# schematic.net
KiCad netlist of a schematic drawn in EasyEDA
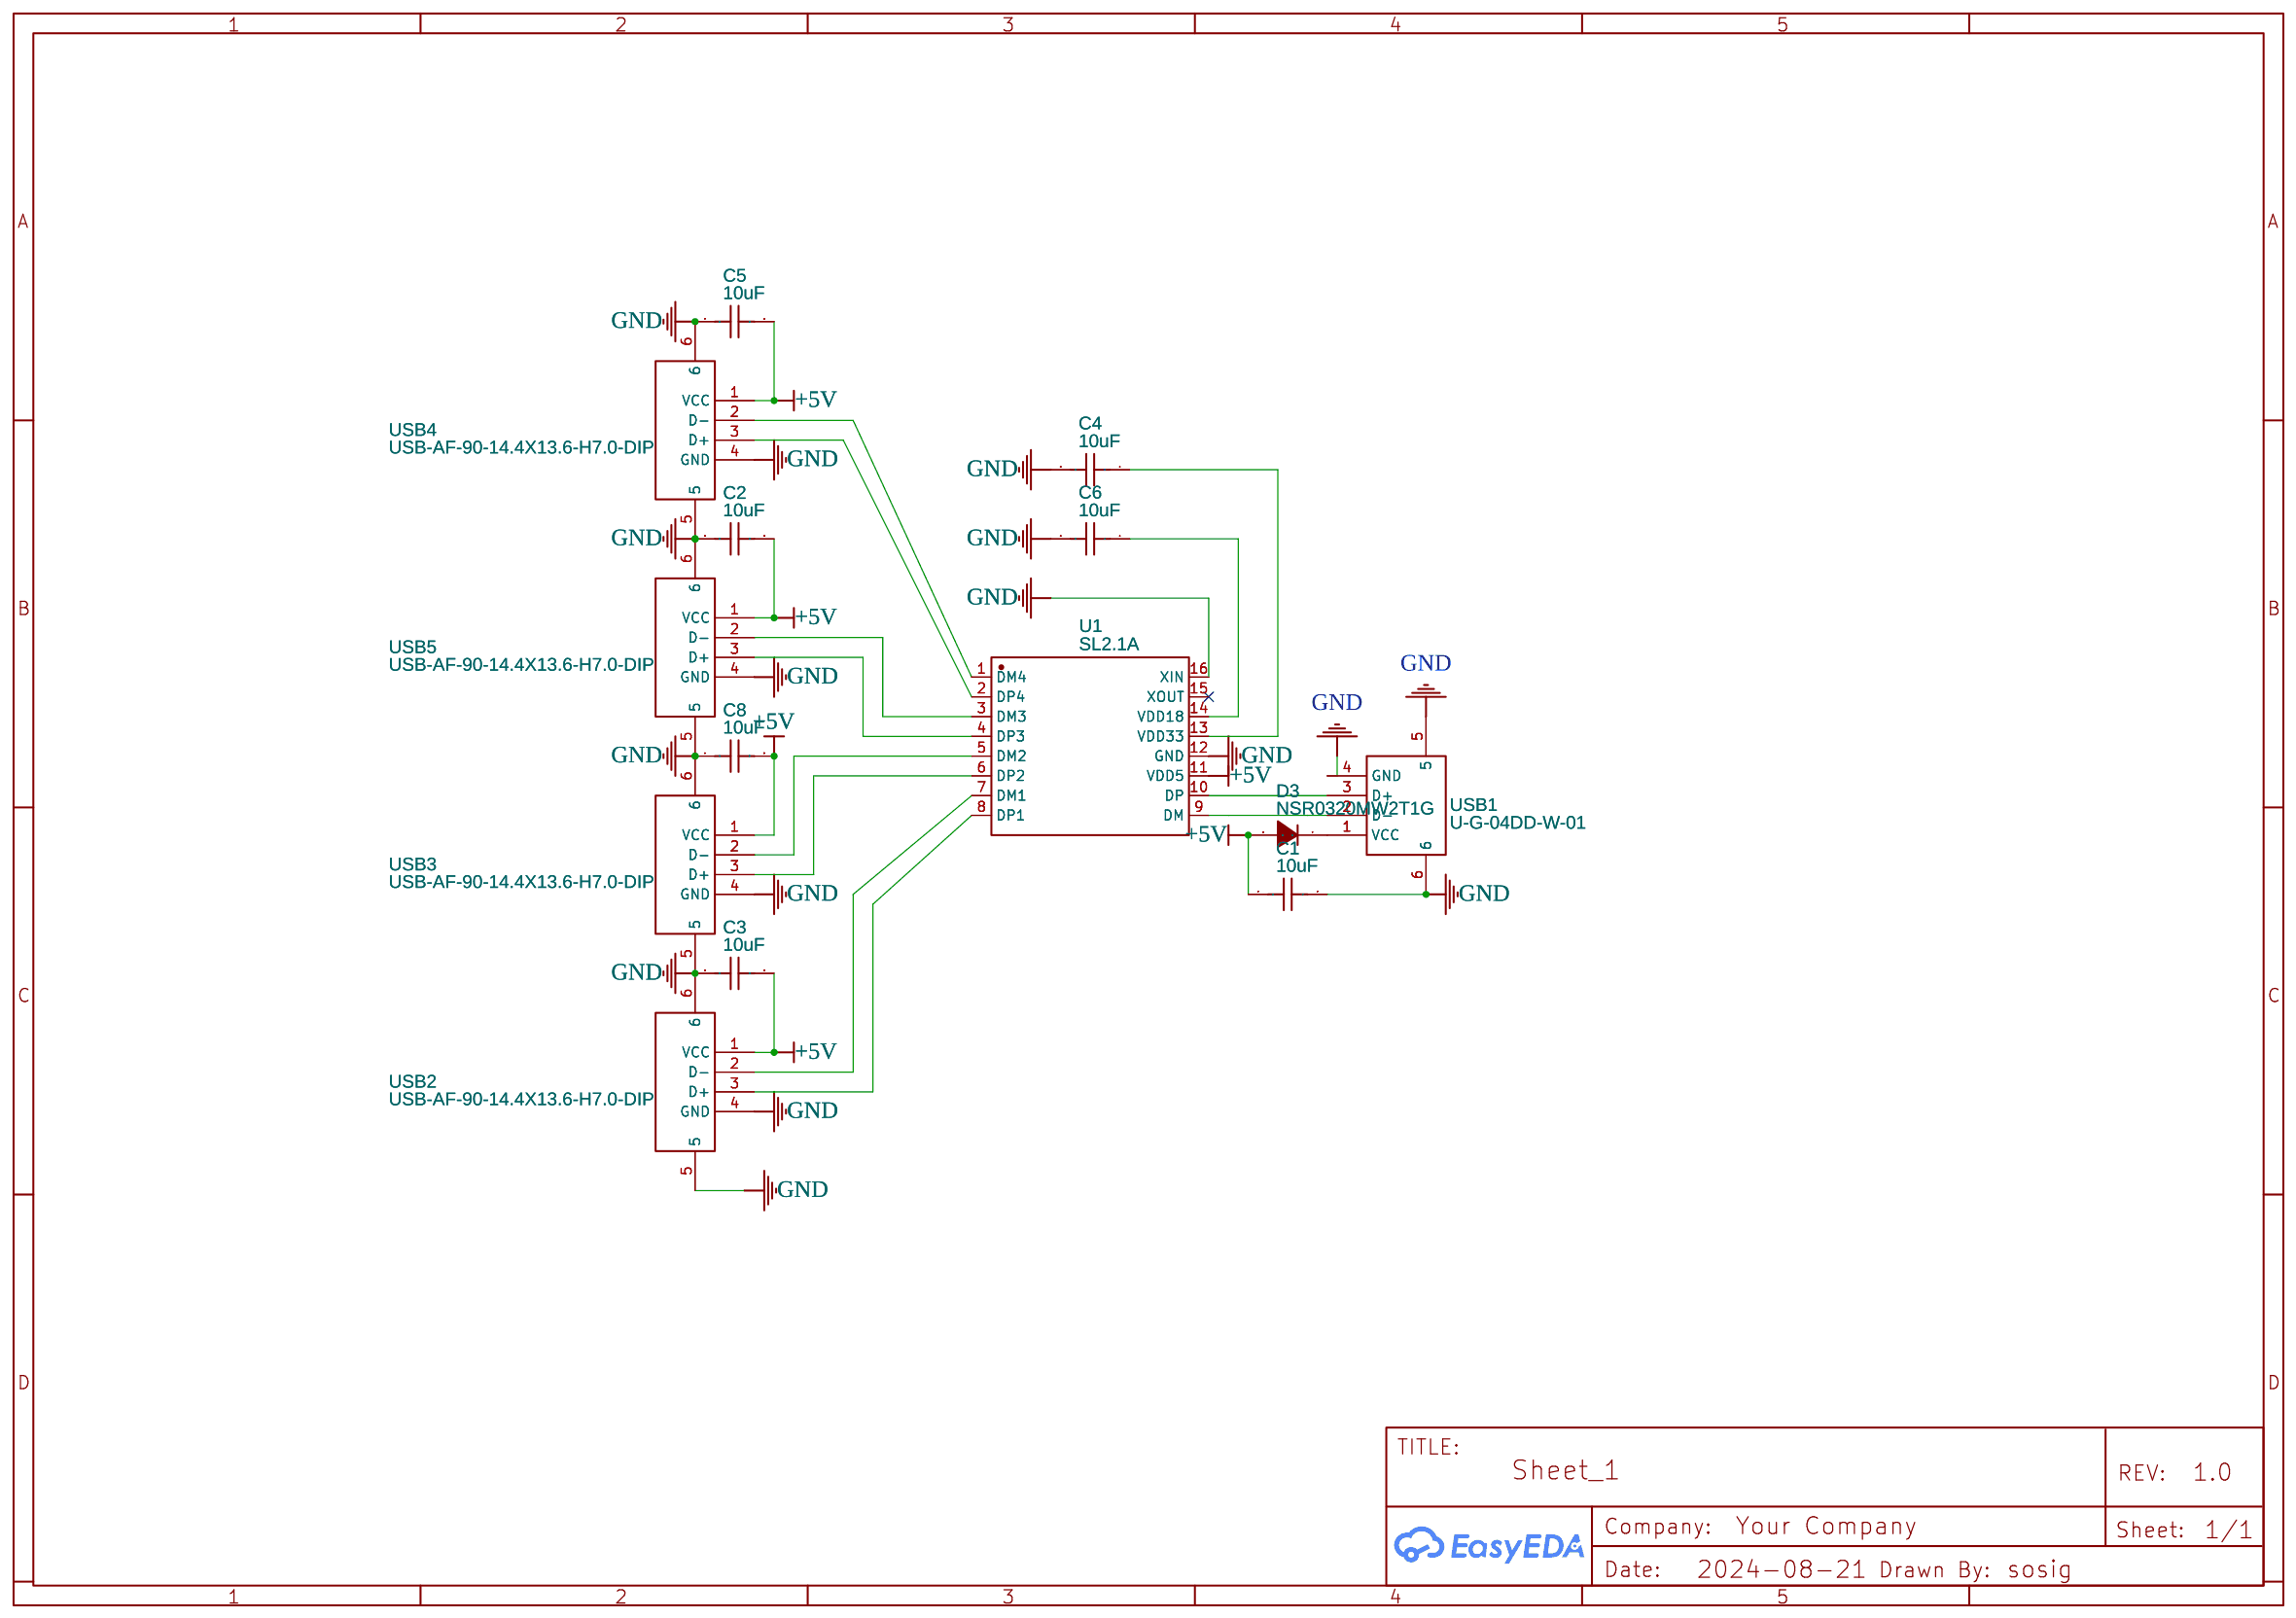
[diagram p0: schematic sheet]

(export (version "E")
  (design (tool "Eeschema 10.0.6"))
  (components
    (comp (ref "C1")
      (value "10uF")
      (fields
        (field (name "Manufacturer Part") "CL10A106KP8NNNC")
        (field (name "Manufacturer") "SAMSUNG(三星)")
      )
      (libsource (lib "") (part "CL10A106KP8NNNC"))
    )
    (comp (ref "C2")
      (value "10uF")
      (fields
        (field (name "Manufacturer Part") "CL10A106KP8NNNC")
        (field (name "Manufacturer") "SAMSUNG(三星)")
      )
      (libsource (lib "") (part "CL10A106KP8NNNC"))
    )
    (comp (ref "C3")
      (value "10uF")
      (fields
        (field (name "Manufacturer Part") "CL10A106KP8NNNC")
        (field (name "Manufacturer") "SAMSUNG(三星)")
      )
      (libsource (lib "") (part "CL10A106KP8NNNC"))
    )
    (comp (ref "C4")
      (value "10uF")
      (fields
        (field (name "Manufacturer Part") "CL10A106KP8NNNC")
        (field (name "Manufacturer") "SAMSUNG(三星)")
      )
      (libsource (lib "") (part "CL10A106KP8NNNC_1"))
    )
    (comp (ref "C5")
      (value "10uF")
      (fields
        (field (name "Manufacturer Part") "CL10A106KP8NNNC")
        (field (name "Manufacturer") "SAMSUNG(三星)")
      )
      (libsource (lib "") (part "CL10A106KP8NNNC"))
    )
    (comp (ref "C6")
      (value "10uF")
      (fields
        (field (name "Manufacturer Part") "CL10A106KP8NNNC")
        (field (name "Manufacturer") "SAMSUNG(三星)")
      )
      (libsource (lib "") (part "CL10A106KP8NNNC_1"))
    )
    (comp (ref "C8")
      (value "10uF")
      (fields
        (field (name "Manufacturer Part") "CL10A106KP8NNNC")
        (field (name "Manufacturer") "SAMSUNG(三星)")
      )
      (libsource (lib "") (part "CL10A106KP8NNNC"))
    )
    (comp (ref "D3")
      (value "NSR0320MW2T1G")
      (fields (field (name "Manufacturer") "onsemi(安森美)"))
      (libsource (lib "") (part "NSR0320MW2T1G"))
    )
    (comp (ref "U1")
      (value "SL2.1A")
      (fields (field (name "Manufacturer") "CoreChips(和芯润德)"))
      (libsource (lib "") (part "SL2.1A"))
    )
    (comp (ref "USB1")
      (value "U-G-04DD-W-01")
      (fields (field (name "Manufacturer Part") "U-G-O4DD-W-1") (field (name "Manufacturer") "韩国韩荣"))
      (libsource (lib "") (part "U-G-04DD-W-01"))
    )
    (comp (ref "USB2")
      (value "USB-AF-90-14.4X13.6-H7.0-DIP")
      (fields (field (name "Manufacturer Part") "903-131A1011D10100") (field (name "Manufacturer") "精拓金"))
      (libsource (lib "") (part "USB-AF-90-14.4X13.6-H7.0-DIP"))
    )
    (comp (ref "USB3")
      (value "USB-AF-90-14.4X13.6-H7.0-DIP")
      (fields (field (name "Manufacturer Part") "903-131A1011D10100") (field (name "Manufacturer") "精拓金"))
      (libsource (lib "") (part "USB-AF-90-14.4X13.6-H7.0-DIP"))
    )
    (comp (ref "USB4")
      (value "USB-AF-90-14.4X13.6-H7.0-DIP")
      (fields (field (name "Manufacturer Part") "903-131A1011D10100") (field (name "Manufacturer") "精拓金"))
      (libsource (lib "") (part "USB-AF-90-14.4X13.6-H7.0-DIP"))
    )
    (comp (ref "USB5")
      (value "USB-AF-90-14.4X13.6-H7.0-DIP")
      (fields (field (name "Manufacturer Part") "903-131A1011D10100") (field (name "Manufacturer") "精拓金"))
      (libsource (lib "") (part "USB-AF-90-14.4X13.6-H7.0-DIP"))
    )
  )
  (nets
    (net (code "1") (name "+5V") (class "Default")
      (node (ref "C1") (pin "1") (pinfunction "1_1") (pintype "unspecified"))
      (node (ref "C2") (pin "2") (pinfunction "2_2") (pintype "unspecified"))
      (node (ref "C3") (pin "2") (pinfunction "2_2") (pintype "unspecified"))
      (node (ref "C5") (pin "2") (pinfunction "2_2") (pintype "unspecified"))
      (node (ref "C8") (pin "2") (pinfunction "2_2") (pintype "unspecified"))
      (node (ref "D3") (pin "2") (pinfunction "A_2") (pintype "unspecified"))
      (node (ref "U1") (pin "11") (pinfunction "VDD5_11") (pintype "unspecified"))
      (node (ref "USB2") (pin "1") (pinfunction "VCC_1") (pintype "unspecified"))
      (node (ref "USB3") (pin "1") (pinfunction "VCC_1") (pintype "unspecified"))
      (node (ref "USB4") (pin "1") (pinfunction "VCC_1") (pintype "unspecified"))
      (node (ref "USB5") (pin "1") (pinfunction "VCC_1") (pintype "unspecified"))
    )
    (net (code "2") (name "GND") (class "Default")
      (node (ref "C1") (pin "2") (pinfunction "2_2") (pintype "unspecified"))
      (node (ref "C2") (pin "1") (pinfunction "1_1") (pintype "unspecified"))
      (node (ref "C3") (pin "1") (pinfunction "1_1") (pintype "unspecified"))
      (node (ref "C4") (pin "2") (pinfunction "2_2") (pintype "unspecified"))
      (node (ref "C5") (pin "1") (pinfunction "1_1") (pintype "unspecified"))
      (node (ref "C6") (pin "2") (pinfunction "2_2") (pintype "unspecified"))
      (node (ref "C8") (pin "1") (pinfunction "1_1") (pintype "unspecified"))
      (node (ref "U1") (pin "12") (pinfunction "GND_12") (pintype "unspecified"))
      (node (ref "U1") (pin "16") (pinfunction "XIN_16") (pintype "unspecified"))
      (node (ref "USB1") (pin "4") (pinfunction "GND_4") (pintype "unspecified"))
      (node (ref "USB1") (pin "5") (pinfunction "5_5") (pintype "unspecified"))
      (node (ref "USB1") (pin "6") (pinfunction "6_6") (pintype "unspecified"))
      (node (ref "USB2") (pin "4") (pinfunction "GND_4") (pintype "unspecified"))
      (node (ref "USB2") (pin "5") (pinfunction "5_5") (pintype "unspecified"))
      (node (ref "USB2") (pin "6") (pinfunction "6_6") (pintype "unspecified"))
      (node (ref "USB3") (pin "4") (pinfunction "GND_4") (pintype "unspecified"))
      (node (ref "USB3") (pin "5") (pinfunction "5_5") (pintype "unspecified"))
      (node (ref "USB3") (pin "6") (pinfunction "6_6") (pintype "unspecified"))
      (node (ref "USB4") (pin "4") (pinfunction "GND_4") (pintype "unspecified"))
      (node (ref "USB4") (pin "5") (pinfunction "5_5") (pintype "unspecified"))
      (node (ref "USB4") (pin "6") (pinfunction "6_6") (pintype "unspecified"))
      (node (ref "USB5") (pin "4") (pinfunction "GND_4") (pintype "unspecified"))
      (node (ref "USB5") (pin "5") (pinfunction "5_5") (pintype "unspecified"))
      (node (ref "USB5") (pin "6") (pinfunction "6_6") (pintype "unspecified"))
    )
    (net (code "3") (name "Net-(D3-C)") (class "Default")
      (node (ref "D3") (pin "1") (pinfunction "C_1") (pintype "unspecified"))
      (node (ref "USB1") (pin "1") (pinfunction "VCC_1") (pintype "unspecified"))
    )
    (net (code "4") (name "Net-(U1-DM)") (class "Default")
      (node (ref "U1") (pin "9") (pinfunction "DM_9") (pintype "unspecified"))
      (node (ref "USB1") (pin "2") (pinfunction "D-_2") (pintype "unspecified"))
    )
    (net (code "5") (name "Net-(U1-DM1)") (class "Default")
      (node (ref "U1") (pin "7") (pinfunction "DM1_7") (pintype "unspecified"))
      (node (ref "USB2") (pin "2") (pinfunction "D-_2") (pintype "unspecified"))
    )
    (net (code "6") (name "Net-(U1-DM2)") (class "Default")
      (node (ref "U1") (pin "5") (pinfunction "DM2_5") (pintype "unspecified"))
      (node (ref "USB3") (pin "2") (pinfunction "D-_2") (pintype "unspecified"))
    )
    (net (code "7") (name "Net-(U1-DM3)") (class "Default")
      (node (ref "U1") (pin "3") (pinfunction "DM3_3") (pintype "unspecified"))
      (node (ref "USB5") (pin "2") (pinfunction "D-_2") (pintype "unspecified"))
    )
    (net (code "8") (name "Net-(U1-DM4)") (class "Default")
      (node (ref "U1") (pin "1") (pinfunction "DM4_1") (pintype "unspecified"))
      (node (ref "USB4") (pin "2") (pinfunction "D-_2") (pintype "unspecified"))
    )
    (net (code "9") (name "Net-(U1-DP)") (class "Default")
      (node (ref "U1") (pin "10") (pinfunction "DP_10") (pintype "unspecified"))
      (node (ref "USB1") (pin "3") (pinfunction "D+_3") (pintype "unspecified"))
    )
    (net (code "10") (name "Net-(U1-DP1)") (class "Default")
      (node (ref "U1") (pin "8") (pinfunction "DP1_8") (pintype "unspecified"))
      (node (ref "USB2") (pin "3") (pinfunction "D+_3") (pintype "unspecified"))
    )
    (net (code "11") (name "Net-(U1-DP2)") (class "Default")
      (node (ref "U1") (pin "6") (pinfunction "DP2_6") (pintype "unspecified"))
      (node (ref "USB3") (pin "3") (pinfunction "D+_3") (pintype "unspecified"))
    )
    (net (code "12") (name "Net-(U1-DP3)") (class "Default")
      (node (ref "U1") (pin "4") (pinfunction "DP3_4") (pintype "unspecified"))
      (node (ref "USB5") (pin "3") (pinfunction "D+_3") (pintype "unspecified"))
    )
    (net (code "13") (name "Net-(U1-DP4)") (class "Default")
      (node (ref "U1") (pin "2") (pinfunction "DP4_2") (pintype "unspecified"))
      (node (ref "USB4") (pin "3") (pinfunction "D+_3") (pintype "unspecified"))
    )
    (net (code "14") (name "Net-(U1-VDD18)") (class "Default")
      (node (ref "C6") (pin "1") (pinfunction "1_1") (pintype "unspecified"))
      (node (ref "U1") (pin "14") (pinfunction "VDD18_14") (pintype "unspecified"))
    )
    (net (code "15") (name "Net-(U1-VDD33)") (class "Default")
      (node (ref "C4") (pin "1") (pinfunction "1_1") (pintype "unspecified"))
      (node (ref "U1") (pin "13") (pinfunction "VDD33_13") (pintype "unspecified"))
    )
    (net (code "16") (name "unconnected-(U1-XOUT-Pad15)") (class "Default")
      (node (ref "U1") (pin "15") (pinfunction "XOUT_15") (pintype "unspecified+no_connect"))
    )
  )
)
